# Sheet1.net
KiCad netlist of a schematic drawn in Altium Designer
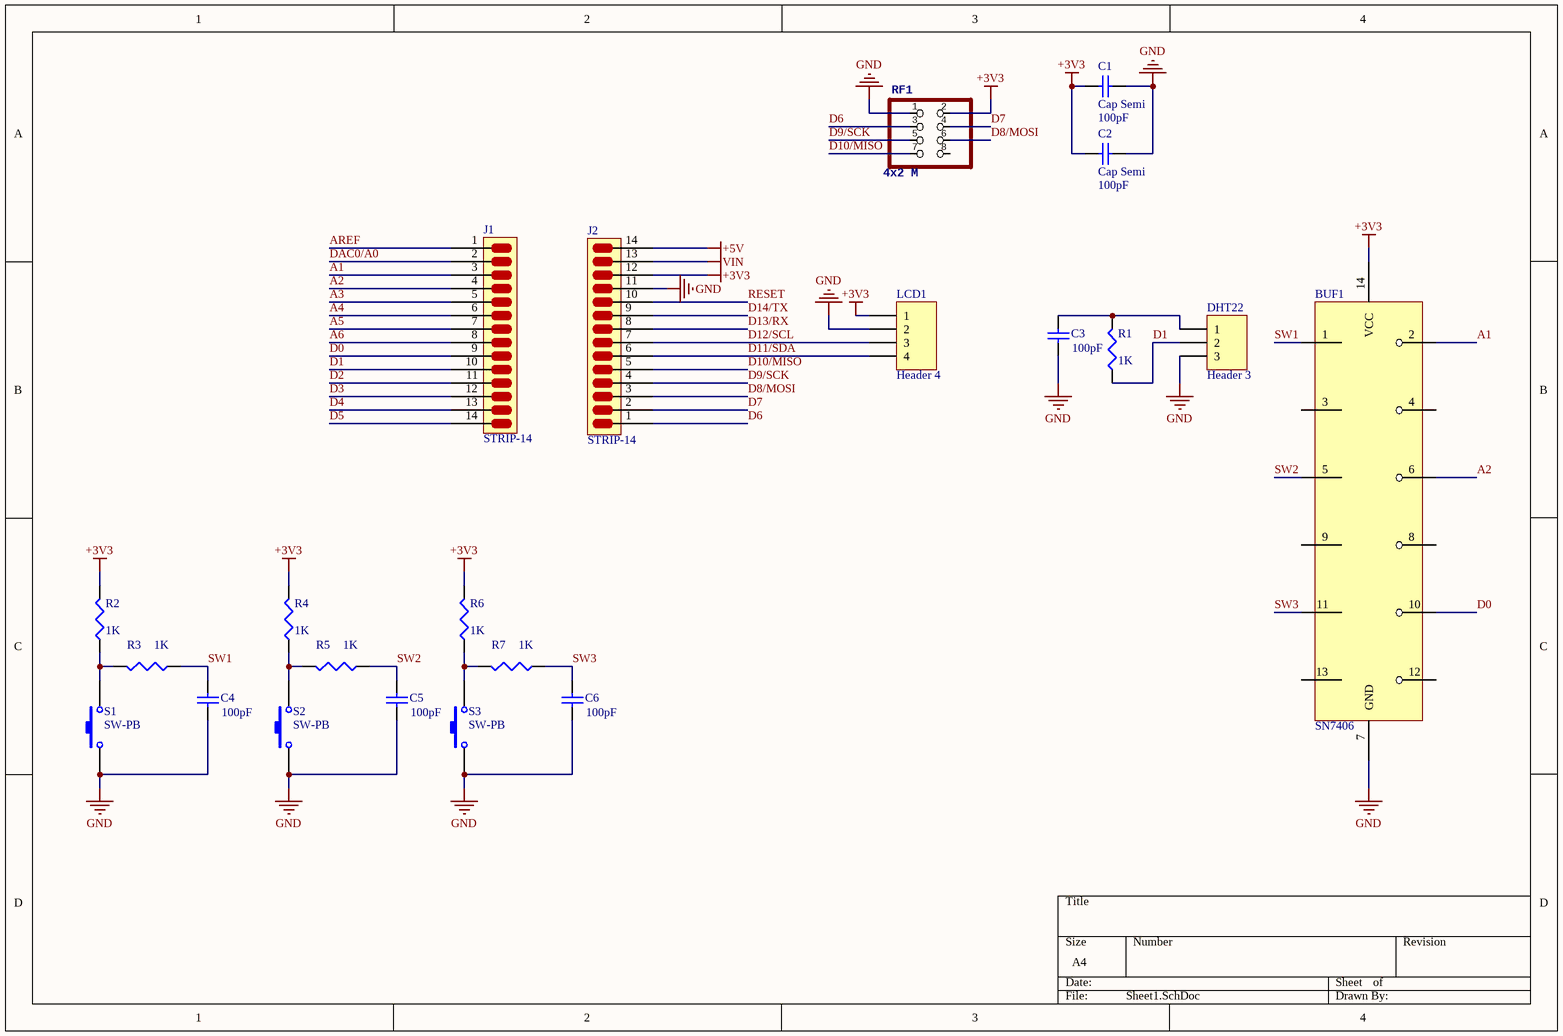
[diagram p0: Sheet1.SchDoc]

(export (version "E")
  (design (tool "Eeschema 10.0.6"))
  (components
    (comp (ref "BUF1") (value "SN7406") (footprint "DIP14") (libsource (lib "Schlib1") (part "SN7406")))
    (comp (ref "C1")
      (value "Cap Semi")
      (footprint "C1206")
      (description "Capacitor (Semiconductor SIM Model)")
      (fields (field (name "ALTIUM_VALUE") "100pF") (field (name "PUBLISHER") "Altium Limited"))
      (libsource (lib "Miscellaneous Devices") (part "Cap Semi"))
    )
    (comp (ref "C2")
      (value "Cap Semi")
      (footprint "C1206")
      (description "Capacitor (Semiconductor SIM Model)")
      (fields (field (name "ALTIUM_VALUE") "100pF") (field (name "PUBLISHER") "Altium Limited"))
      (libsource (lib "Miscellaneous Devices") (part "Cap Semi"))
    )
    (comp (ref "C3")
      (value "100pF")
      (footprint "C1206")
      (description "Capacitor (Semiconductor SIM Model)")
      (fields (field (name "Comment") "Cap Semi") (field (name "PUBLISHER") "Altium Limited"))
      (libsource (lib "Miscellaneous Devices") (part "Cap Semi"))
    )
    (comp (ref "C4")
      (value "100pF")
      (footprint "C1206")
      (description "Capacitor (Semiconductor SIM Model)")
      (fields (field (name "Comment") "Cap Semi") (field (name "PUBLISHER") "Altium Limited"))
      (libsource (lib "Miscellaneous Devices") (part "Cap Semi"))
    )
    (comp (ref "C5")
      (value "100pF")
      (footprint "C1206")
      (description "Capacitor (Semiconductor SIM Model)")
      (fields (field (name "Comment") "Cap Semi") (field (name "PUBLISHER") "Altium Limited"))
      (libsource (lib "Miscellaneous Devices") (part "Cap Semi"))
    )
    (comp (ref "C6")
      (value "100pF")
      (footprint "C1206")
      (description "Capacitor (Semiconductor SIM Model)")
      (fields (field (name "Comment") "Cap Semi") (field (name "PUBLISHER") "Altium Limited"))
      (libsource (lib "Miscellaneous Devices") (part "Cap Semi"))
    )
    (comp (ref "DHT22")
      (value "Header 3")
      (footprint "HDR1X3")
      (description "Header, 3-Pin")
      (fields (field (name "PUBLISHER") "Altium Limited"))
      (libsource (lib "Miscellaneous Connectors") (part "Header 3"))
    )
    (comp (ref "J1") (value "STRIP-14") (footprint "STRIP-14") (libsource (lib "Schlib1") (part "STRIP-14")))
    (comp (ref "J2") (value "STRIP-14") (footprint "STRIP-14") (libsource (lib "") (part "STRIP-14_1")))
    (comp (ref "LCD1")
      (value "Header 4")
      (footprint "HDR1X4")
      (description "Header, 4-Pin")
      (fields (field (name "PUBLISHER") "Altium Limited"))
      (libsource (lib "Miscellaneous Connectors") (part "Header 4"))
    )
    (comp (ref "R1")
      (value "1K")
      (footprint "J1-0603")
      (description "Resistor")
      (fields (field (name "Comment") "Res3") (field (name "PUBLISHER") "Altium Limited"))
      (libsource (lib "Miscellaneous Devices") (part "Res3"))
    )
    (comp (ref "R2")
      (value "1K")
      (footprint "J1-0603")
      (description "Resistor")
      (fields (field (name "Comment") "Res3") (field (name "PUBLISHER") "Altium Limited"))
      (libsource (lib "Miscellaneous Devices") (part "Res3"))
    )
    (comp (ref "R3")
      (value "1K")
      (footprint "J1-0603")
      (description "Resistor")
      (fields (field (name "Comment") "Res3") (field (name "PUBLISHER") "Altium Limited"))
      (libsource (lib "Miscellaneous Devices") (part "Res3"))
    )
    (comp (ref "R4")
      (value "1K")
      (footprint "J1-0603")
      (description "Resistor")
      (fields (field (name "Comment") "Res3") (field (name "PUBLISHER") "Altium Limited"))
      (libsource (lib "Miscellaneous Devices") (part "Res3"))
    )
    (comp (ref "R5")
      (value "1K")
      (footprint "J1-0603")
      (description "Resistor")
      (fields (field (name "Comment") "Res3") (field (name "PUBLISHER") "Altium Limited"))
      (libsource (lib "Miscellaneous Devices") (part "Res3"))
    )
    (comp (ref "R6")
      (value "1K")
      (footprint "J1-0603")
      (description "Resistor")
      (fields (field (name "Comment") "Res3") (field (name "PUBLISHER") "Altium Limited"))
      (libsource (lib "Miscellaneous Devices") (part "Res3"))
    )
    (comp (ref "R7")
      (value "1K")
      (footprint "J1-0603")
      (description "Resistor")
      (fields (field (name "Comment") "Res3") (field (name "PUBLISHER") "Altium Limited"))
      (libsource (lib "Miscellaneous Devices") (part "Res3"))
    )
    (comp (ref "RF1")
      (value "4x2 M")
      (footprint "2X04")
      (fields (field (name "PARTNO") "M20-9980345"))
      (libsource (lib "Schlib1") (part "PINHD-2X4"))
    )
    (comp (ref "S1")
      (value "SW-PB")
      (footprint "1080")
      (description "Switch")
      (fields (field (name "PUBLISHER") "Altium Limited"))
      (libsource (lib "Miscellaneous Devices") (part "SW-PB"))
    )
    (comp (ref "S2")
      (value "SW-PB")
      (footprint "1080")
      (description "Switch")
      (fields (field (name "PUBLISHER") "Altium Limited"))
      (libsource (lib "Miscellaneous Devices") (part "SW-PB"))
    )
    (comp (ref "S3")
      (value "SW-PB")
      (footprint "1080")
      (description "Switch")
      (fields (field (name "PUBLISHER") "Altium Limited"))
      (libsource (lib "Miscellaneous Devices") (part "SW-PB"))
    )
  )
  (nets
    (net (code "1") (name "+3V3") (class "Default")
      (node (ref "BUF1") (pin "14") (pinfunction "VCC_14") (pintype "passive"))
      (node (ref "C1") (pin "1") (pinfunction "1_1") (pintype "passive"))
      (node (ref "C2") (pin "1") (pinfunction "1_1") (pintype "passive"))
      (node (ref "J2") (pin "12") (pinfunction "12_12") (pintype "passive"))
      (node (ref "LCD1") (pin "1") (pinfunction "1_1") (pintype "passive"))
      (node (ref "R2") (pin "2") (pinfunction "2_2") (pintype "passive"))
      (node (ref "R4") (pin "2") (pinfunction "2_2") (pintype "passive"))
      (node (ref "R6") (pin "2") (pinfunction "2_2") (pintype "passive"))
      (node (ref "RF1") (pin "2") (pinfunction "2_2") (pintype "passive"))
    )
    (net (code "2") (name "+5V") (class "Default")
      (node (ref "J2") (pin "14") (pinfunction "14_14") (pintype "passive"))
    )
    (net (code "3") (name "/A1") (class "Default")
      (node (ref "BUF1") (pin "2") (pinfunction "2_2") (pintype "passive"))
      (node (ref "J1") (pin "3") (pinfunction "3_3") (pintype "passive"))
    )
    (net (code "4") (name "/A2") (class "Default")
      (node (ref "BUF1") (pin "6") (pinfunction "6_6") (pintype "passive"))
      (node (ref "J1") (pin "4") (pinfunction "4_4") (pintype "passive"))
    )
    (net (code "5") (name "/A3") (class "Default")
      (node (ref "J1") (pin "5") (pinfunction "5_5") (pintype "passive"))
    )
    (net (code "6") (name "/A4") (class "Default")
      (node (ref "J1") (pin "6") (pinfunction "6_6") (pintype "passive"))
    )
    (net (code "7") (name "/A5") (class "Default")
      (node (ref "J1") (pin "7") (pinfunction "7_7") (pintype "passive"))
    )
    (net (code "8") (name "/A6") (class "Default")
      (node (ref "J1") (pin "8") (pinfunction "8_8") (pintype "passive"))
    )
    (net (code "9") (name "/AREF") (class "Default")
      (node (ref "J1") (pin "1") (pinfunction "1_1") (pintype "passive"))
    )
    (net (code "10") (name "/D0") (class "Default")
      (node (ref "BUF1") (pin "10") (pinfunction "10_10") (pintype "passive"))
      (node (ref "J1") (pin "9") (pinfunction "9_9") (pintype "passive"))
    )
    (net (code "11") (name "/D1") (class "Default")
      (node (ref "DHT22") (pin "2") (pinfunction "2_2") (pintype "passive"))
      (node (ref "J1") (pin "10") (pinfunction "10_10") (pintype "passive"))
      (node (ref "R1") (pin "1") (pinfunction "1_1") (pintype "passive"))
    )
    (net (code "12") (name "/D2") (class "Default")
      (node (ref "J1") (pin "11") (pinfunction "11_11") (pintype "passive"))
    )
    (net (code "13") (name "/D3") (class "Default")
      (node (ref "J1") (pin "12") (pinfunction "12_12") (pintype "passive"))
    )
    (net (code "14") (name "/D4") (class "Default")
      (node (ref "J1") (pin "13") (pinfunction "13_13") (pintype "passive"))
    )
    (net (code "15") (name "/D5") (class "Default")
      (node (ref "J1") (pin "14") (pinfunction "14_14") (pintype "passive"))
    )
    (net (code "16") (name "/D6") (class "Default")
      (node (ref "J2") (pin "1") (pinfunction "1_1") (pintype "passive"))
      (node (ref "RF1") (pin "3") (pinfunction "3_3") (pintype "passive"))
    )
    (net (code "17") (name "/D7") (class "Default")
      (node (ref "J2") (pin "2") (pinfunction "2_2") (pintype "passive"))
      (node (ref "RF1") (pin "4") (pinfunction "4_4") (pintype "passive"))
    )
    (net (code "18") (name "/D8{slash}MOSI") (class "Default")
      (node (ref "J2") (pin "3") (pinfunction "3_3") (pintype "passive"))
      (node (ref "RF1") (pin "6") (pinfunction "6_6") (pintype "passive"))
    )
    (net (code "19") (name "/D9{slash}SCK") (class "Default")
      (node (ref "J2") (pin "4") (pinfunction "4_4") (pintype "passive"))
      (node (ref "RF1") (pin "5") (pinfunction "5_5") (pintype "passive"))
    )
    (net (code "20") (name "/D10{slash}MISO") (class "Default")
      (node (ref "J2") (pin "5") (pinfunction "5_5") (pintype "passive"))
      (node (ref "RF1") (pin "7") (pinfunction "7_7") (pintype "passive"))
    )
    (net (code "21") (name "/D11{slash}SDA") (class "Default")
      (node (ref "J2") (pin "6") (pinfunction "6_6") (pintype "passive"))
      (node (ref "LCD1") (pin "4") (pinfunction "4_4") (pintype "passive"))
    )
    (net (code "22") (name "/D12{slash}SCL") (class "Default")
      (node (ref "J2") (pin "7") (pinfunction "7_7") (pintype "passive"))
      (node (ref "LCD1") (pin "3") (pinfunction "3_3") (pintype "passive"))
    )
    (net (code "23") (name "/D13{slash}RX") (class "Default")
      (node (ref "J2") (pin "8") (pinfunction "8_8") (pintype "passive"))
    )
    (net (code "24") (name "/D14{slash}TX") (class "Default")
      (node (ref "J2") (pin "9") (pinfunction "9_9") (pintype "passive"))
    )
    (net (code "25") (name "/DAC0{slash}A0") (class "Default")
      (node (ref "J1") (pin "2") (pinfunction "2_2") (pintype "passive"))
    )
    (net (code "26") (name "/RESET") (class "Default")
      (node (ref "J2") (pin "10") (pinfunction "10_10") (pintype "passive"))
    )
    (net (code "27") (name "/SW1") (class "Default")
      (node (ref "BUF1") (pin "1") (pinfunction "1_1") (pintype "passive"))
      (node (ref "C4") (pin "2") (pinfunction "2_2") (pintype "passive"))
      (node (ref "R3") (pin "1") (pinfunction "1_1") (pintype "passive"))
    )
    (net (code "28") (name "/SW2") (class "Default")
      (node (ref "BUF1") (pin "5") (pinfunction "5_5") (pintype "passive"))
      (node (ref "C5") (pin "2") (pinfunction "2_2") (pintype "passive"))
      (node (ref "R5") (pin "1") (pinfunction "1_1") (pintype "passive"))
    )
    (net (code "29") (name "/SW3") (class "Default")
      (node (ref "BUF1") (pin "11") (pinfunction "11_11") (pintype "passive"))
      (node (ref "C6") (pin "2") (pinfunction "2_2") (pintype "passive"))
      (node (ref "R7") (pin "1") (pinfunction "1_1") (pintype "passive"))
    )
    (net (code "30") (name "GND") (class "Default")
      (node (ref "BUF1") (pin "7") (pinfunction "GND_7") (pintype "passive"))
      (node (ref "C1") (pin "2") (pinfunction "2_2") (pintype "passive"))
      (node (ref "C2") (pin "2") (pinfunction "2_2") (pintype "passive"))
      (node (ref "C3") (pin "1") (pinfunction "1_1") (pintype "passive"))
      (node (ref "C4") (pin "1") (pinfunction "1_1") (pintype "passive"))
      (node (ref "C5") (pin "1") (pinfunction "1_1") (pintype "passive"))
      (node (ref "C6") (pin "1") (pinfunction "1_1") (pintype "passive"))
      (node (ref "DHT22") (pin "3") (pinfunction "3_3") (pintype "passive"))
      (node (ref "J2") (pin "11") (pinfunction "11_11") (pintype "passive"))
      (node (ref "LCD1") (pin "2") (pinfunction "2_2") (pintype "passive"))
      (node (ref "RF1") (pin "1") (pinfunction "1_1") (pintype "passive"))
      (node (ref "S1") (pin "1") (pinfunction "1_1") (pintype "passive"))
      (node (ref "S2") (pin "1") (pinfunction "1_1") (pintype "passive"))
      (node (ref "S3") (pin "1") (pinfunction "1_1") (pintype "passive"))
    )
    (net (code "31") (name "Net-(C3-Pad2)") (class "Default")
      (node (ref "C3") (pin "2") (pinfunction "2_2") (pintype "passive"))
      (node (ref "DHT22") (pin "1") (pinfunction "1_1") (pintype "passive"))
      (node (ref "R1") (pin "2") (pinfunction "2_2") (pintype "passive"))
    )
    (net (code "32") (name "Net-(R2-Pad1)") (class "Default")
      (node (ref "R2") (pin "1") (pinfunction "1_1") (pintype "passive"))
      (node (ref "R3") (pin "2") (pinfunction "2_2") (pintype "passive"))
      (node (ref "S1") (pin "2") (pinfunction "2_2") (pintype "passive"))
    )
    (net (code "33") (name "Net-(R4-Pad1)") (class "Default")
      (node (ref "R4") (pin "1") (pinfunction "1_1") (pintype "passive"))
      (node (ref "R5") (pin "2") (pinfunction "2_2") (pintype "passive"))
      (node (ref "S2") (pin "2") (pinfunction "2_2") (pintype "passive"))
    )
    (net (code "34") (name "Net-(R6-Pad1)") (class "Default")
      (node (ref "R6") (pin "1") (pinfunction "1_1") (pintype "passive"))
      (node (ref "R7") (pin "2") (pinfunction "2_2") (pintype "passive"))
      (node (ref "S3") (pin "2") (pinfunction "2_2") (pintype "passive"))
    )
    (net (code "35") (name "VIN") (class "Default")
      (node (ref "J2") (pin "13") (pinfunction "13_13") (pintype "passive"))
    )
    (net (code "36") (name "unconnected-(BUF1-Pad3)") (class "Default")
      (node (ref "BUF1") (pin "3") (pinfunction "3_3") (pintype "passive"))
    )
    (net (code "37") (name "unconnected-(BUF1-Pad4)") (class "Default")
      (node (ref "BUF1") (pin "4") (pinfunction "4_4") (pintype "passive"))
    )
    (net (code "38") (name "unconnected-(BUF1-Pad8)") (class "Default")
      (node (ref "BUF1") (pin "8") (pinfunction "8_8") (pintype "passive"))
    )
    (net (code "39") (name "unconnected-(BUF1-Pad9)") (class "Default")
      (node (ref "BUF1") (pin "9") (pinfunction "9_9") (pintype "passive"))
    )
    (net (code "40") (name "unconnected-(BUF1-Pad12)") (class "Default")
      (node (ref "BUF1") (pin "12") (pinfunction "12_12") (pintype "passive"))
    )
    (net (code "41") (name "unconnected-(BUF1-Pad13)") (class "Default")
      (node (ref "BUF1") (pin "13") (pinfunction "13_13") (pintype "passive"))
    )
    (net (code "42") (name "unconnected-(RF1-Pad8)") (class "Default")
      (node (ref "RF1") (pin "8") (pinfunction "8_8") (pintype "passive"))
    )
  )
)
